# Sheet1.net
KiCad netlist of a schematic drawn in Altium Designer
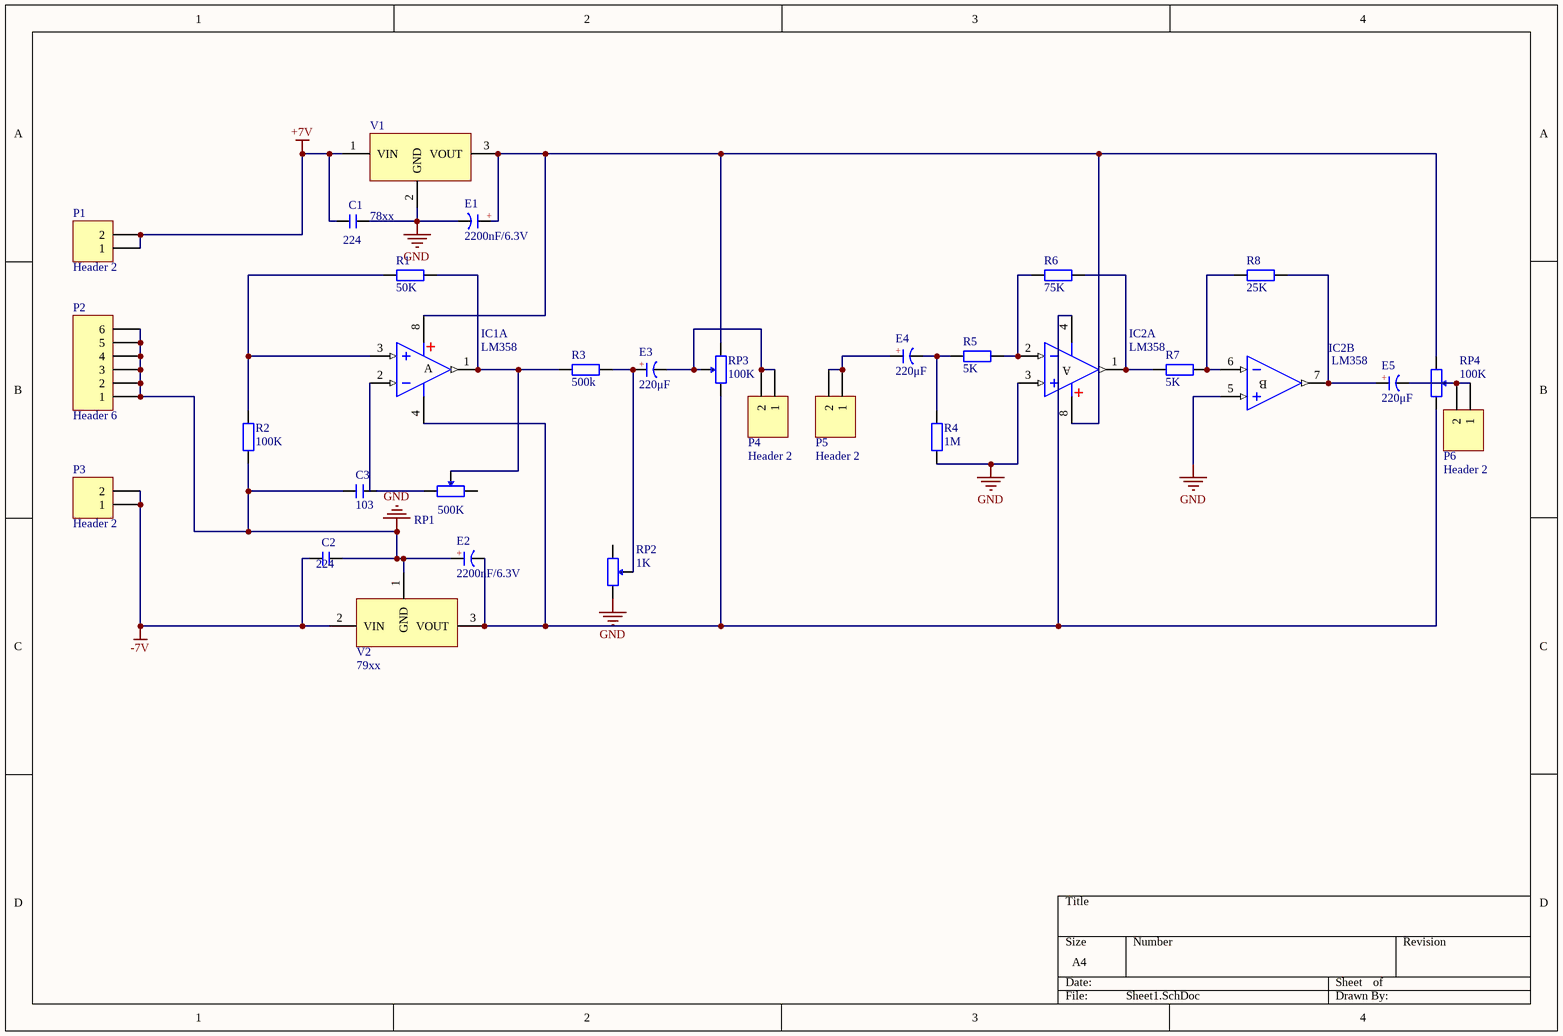
[diagram p0: Sheet1.SchDoc]

(export (version "E")
  (design (tool "Eeschema 10.0.6"))
  (components
    (comp (ref "C1")
      (value "224")
      (footprint "C 0805_L")
      (description "无极性贴片电容")
      (fields (field (name "版权归属") "源创客"))
      (libsource (lib "3.1   - 电阻-电容-电感") (part "C"))
    )
    (comp (ref "C2")
      (value "224")
      (footprint "C 0805_L")
      (description "无极性贴片电容")
      (fields (field (name "版权归属") "源创客"))
      (libsource (lib "3.1   - 电阻-电容-电感") (part "C"))
    )
    (comp (ref "C3")
      (value "103")
      (footprint "C 0805_L")
      (description "无极性贴片电容")
      (fields (field (name "版权归属") "源创客"))
      (libsource (lib "3.1   - 电阻-电容-电感") (part "C"))
    )
    (comp (ref "E1")
      (value "2200nF/6.3V")
      (footprint "CS 5.0*10*13 - C")
      (description "直插固态电容")
      (fields (field (name "版权归属") "源创客"))
      (libsource (lib "") (part "C-CS_1"))
    )
    (comp (ref "E2")
      (value "2200nF/6.3V")
      (footprint "CS 5.0*10*13 - C")
      (description "直插固态电容")
      (fields (field (name "版权归属") "源创客"))
      (libsource (lib "3.1   - 电阻-电容-电感") (part "C-CS"))
    )
    (comp (ref "E3")
      (value "220μF")
      (footprint "CS 2.5*6.3*11 - C")
      (description "直插固态电容")
      (fields (field (name "版权归属") "源创客"))
      (libsource (lib "3.1   - 电阻-电容-电感") (part "C-CS"))
    )
    (comp (ref "E4")
      (value "220μF")
      (footprint "CS 2.0*5*8 - C")
      (description "直插固态电容")
      (fields (field (name "版权归属") "源创客"))
      (libsource (lib "3.1   - 电阻-电容-电感") (part "C-CS"))
    )
    (comp (ref "E5")
      (value "220μF")
      (footprint "CS 2.0*5*8 - C")
      (description "直插固态电容")
      (fields (field (name "版权归属") "源创客"))
      (libsource (lib "3.1   - 电阻-电容-电感") (part "C-CS"))
    )
    (comp (ref "IC1")
      (value "LM358")
      (footprint "SOP8_N")
      (description "双路运放")
      (fields (field (name "版权归属") "源创客"))
      (libsource (lib "1.1   - IC芯片") (part "LM358"))
    )
    (comp (ref "IC2")
      (value "LM358")
      (footprint "SOP8_N")
      (description "双路运放")
      (fields (field (name "版权归属") "源创客"))
      (libsource (lib "1.1   - IC芯片") (part "LM358"))
    )
    (comp (ref "P1")
      (value "Header 2")
      (footprint "HDR1X2")
      (description "Header, 2-Pin")
      (fields (field (name "PUBLISHER") "Altium Limited"))
      (libsource (lib "") (part "Header 2_1"))
    )
    (comp (ref "P2")
      (value "Header 6")
      (footprint "HDR1X6")
      (description "Header, 6-Pin")
      (fields (field (name "PUBLISHER") "Altium Limited"))
      (libsource (lib "Miscellaneous Connectors") (part "Header 6"))
    )
    (comp (ref "P3")
      (value "Header 2")
      (footprint "HDR1X2")
      (description "Header, 2-Pin")
      (fields (field (name "PUBLISHER") "Altium Limited"))
      (libsource (lib "") (part "Header 2_1"))
    )
    (comp (ref "P4")
      (value "Header 2")
      (footprint "HDR1X2")
      (description "Header, 2-Pin")
      (fields (field (name "PUBLISHER") "Altium Limited"))
      (libsource (lib "Miscellaneous Connectors") (part "Header 2"))
    )
    (comp (ref "P5")
      (value "Header 2")
      (footprint "HDR1X2")
      (description "Header, 2-Pin")
      (fields (field (name "PUBLISHER") "Altium Limited"))
      (libsource (lib "Miscellaneous Connectors") (part "Header 2"))
    )
    (comp (ref "P6")
      (value "Header 2")
      (footprint "HDR1X2")
      (description "Header, 2-Pin")
      (fields (field (name "PUBLISHER") "Altium Limited"))
      (libsource (lib "Miscellaneous Connectors") (part "Header 2"))
    )
    (comp (ref "R1")
      (value "50K")
      (footprint "R 0805-HP_L")
      (description "精密贴片电阻")
      (fields (field (name "版权归属") "源创客"))
      (libsource (lib "3.1   - 电阻-电容-电感") (part "R-Precision"))
    )
    (comp (ref "R2")
      (value "100K")
      (footprint "R 0805-HP_L")
      (description "精密贴片电阻")
      (fields (field (name "版权归属") "源创客"))
      (libsource (lib "3.1   - 电阻-电容-电感") (part "R-Precision"))
    )
    (comp (ref "R3")
      (value "500k")
      (footprint "RS 1/4W")
      (description "直插色环电阻")
      (fields (field (name "版权归属") "源创客"))
      (libsource (lib "3.1   - 电阻-电容-电感") (part "R-CRR"))
    )
    (comp (ref "R4")
      (value "1M")
      (footprint "RS 1/4W")
      (description "直插色环电阻")
      (fields (field (name "版权归属") "源创客"))
      (libsource (lib "3.1   - 电阻-电容-电感") (part "R-CRR"))
    )
    (comp (ref "R5")
      (value "5K")
      (footprint "R 0805_L")
      (description "贴片电阻")
      (fields (field (name "版权归属") "源创客"))
      (libsource (lib "3.1   - 电阻-电容-电感") (part "R"))
    )
    (comp (ref "R6")
      (value "75K")
      (footprint "R 0805_L")
      (description "贴片电阻")
      (fields (field (name "版权归属") "源创客"))
      (libsource (lib "3.1   - 电阻-电容-电感") (part "R"))
    )
    (comp (ref "R7")
      (value "5K")
      (footprint "R 0805_L")
      (description "贴片电阻")
      (fields (field (name "版权归属") "源创客"))
      (libsource (lib "3.1   - 电阻-电容-电感") (part "R"))
    )
    (comp (ref "R8")
      (value "25K")
      (footprint "R 0805_L")
      (description "贴片电阻")
      (fields (field (name "版权归属") "源创客"))
      (libsource (lib "3.1   - 电阻-电容-电感") (part "R"))
    )
    (comp (ref "RP1")
      (value "500K")
      (footprint "3296W")
      (description "插件单联电位器")
      (fields (field (name "版权归属") "源创客"))
      (libsource (lib "3.1   - 电阻-电容-电感") (part "RP-ID"))
    )
    (comp (ref "RP2")
      (value "1K")
      (footprint "3296W")
      (description "插件单联电位器")
      (fields (field (name "版权归属") "源创客"))
      (libsource (lib "3.1   - 电阻-电容-电感") (part "RP-ID"))
    )
    (comp (ref "RP3")
      (value "100K")
      (footprint "3296W")
      (description "插件单联电位器")
      (fields (field (name "版权归属") "源创客"))
      (libsource (lib "3.1   - 电阻-电容-电感") (part "RP-ID"))
    )
    (comp (ref "RP4")
      (value "100K")
      (footprint "3296W")
      (description "插件单联电位器")
      (fields (field (name "版权归属") "源创客"))
      (libsource (lib "3.1   - 电阻-电容-电感") (part "RP-ID"))
    )
    (comp (ref "V1")
      (value "78xx")
      (footprint "TO220A")
      (description "线性稳压芯片")
      (fields (field (name "版权归属") "源创客"))
      (libsource (lib "1.3   - 电源类芯片") (part "78xx"))
    )
    (comp (ref "V2")
      (value "79xx")
      (footprint "TO220A")
      (description "线性稳压芯片")
      (fields (field (name "版权归属") "源创客"))
      (libsource (lib "1.3   - 电源类芯片") (part "79xx"))
    )
  )
  (nets
    (net (code "1") (name "+7V") (class "Default")
      (node (ref "C1") (pin "1") (pinfunction "1_1") (pintype "passive"))
      (node (ref "P1") (pin "1") (pinfunction "1_1") (pintype "passive"))
      (node (ref "P1") (pin "2") (pinfunction "2_2") (pintype "passive"))
      (node (ref "V1") (pin "1") (pinfunction "VIN_1") (pintype "passive"))
    )
    (net (code "2") (name "-7V") (class "Default")
      (node (ref "C2") (pin "1") (pinfunction "1_1") (pintype "passive"))
      (node (ref "P3") (pin "1") (pinfunction "1_1") (pintype "passive"))
      (node (ref "P3") (pin "2") (pinfunction "2_2") (pintype "passive"))
      (node (ref "V2") (pin "2") (pinfunction "VIN_2") (pintype "passive"))
    )
    (net (code "3") (name "GND") (class "Default")
      (node (ref "C1") (pin "2") (pinfunction "2_2") (pintype "passive"))
      (node (ref "C2") (pin "2") (pinfunction "2_2") (pintype "passive"))
      (node (ref "C3") (pin "1") (pinfunction "1_1") (pintype "passive"))
      (node (ref "E1") (pin "2") (pinfunction "K_2") (pintype "passive"))
      (node (ref "E2") (pin "1") (pinfunction "A_1") (pintype "passive"))
      (node (ref "IC2") (pin "3") (pinfunction "IN+_3") (pintype "input"))
      (node (ref "IC2") (pin "5") (pinfunction "IN+_5") (pintype "input"))
      (node (ref "P2") (pin "1") (pinfunction "1_1") (pintype "passive"))
      (node (ref "P2") (pin "2") (pinfunction "2_2") (pintype "passive"))
      (node (ref "P2") (pin "3") (pinfunction "3_3") (pintype "passive"))
      (node (ref "P2") (pin "4") (pinfunction "4_4") (pintype "passive"))
      (node (ref "P2") (pin "5") (pinfunction "5_5") (pintype "passive"))
      (node (ref "P2") (pin "6") (pinfunction "6_6") (pintype "passive"))
      (node (ref "R2") (pin "1") (pinfunction "1_1") (pintype "passive"))
      (node (ref "R4") (pin "1") (pinfunction "1_1") (pintype "passive"))
      (node (ref "RP2") (pin "3") (pinfunction "3_3") (pintype "passive"))
      (node (ref "V1") (pin "2") (pinfunction "GND_2") (pintype "passive"))
      (node (ref "V2") (pin "1") (pinfunction "GND_1") (pintype "passive"))
    )
    (net (code "4") (name "Net-(C3-Pad2)") (class "Default")
      (node (ref "C3") (pin "2") (pinfunction "2_2") (pintype "passive"))
      (node (ref "RP1") (pin "1") (pinfunction "1_1") (pintype "passive"))
    )
    (net (code "5") (name "Net-(E1-A)") (class "Default")
      (node (ref "E1") (pin "1") (pinfunction "A_1") (pintype "passive"))
      (node (ref "IC1") (pin "8") (pinfunction "V+_8") (pintype "power_in"))
      (node (ref "IC2") (pin "8") (pinfunction "V+_8") (pintype "power_in"))
      (node (ref "RP3") (pin "3") (pinfunction "3_3") (pintype "passive"))
      (node (ref "RP4") (pin "1") (pinfunction "1_1") (pintype "passive"))
      (node (ref "V1") (pin "3") (pinfunction "VOUT_3") (pintype "passive"))
    )
    (net (code "6") (name "Net-(E2-K)") (class "Default")
      (node (ref "E2") (pin "2") (pinfunction "K_2") (pintype "passive"))
      (node (ref "IC1") (pin "4") (pinfunction "V-_4") (pintype "power_in"))
      (node (ref "IC2") (pin "4") (pinfunction "V-_4") (pintype "power_in"))
      (node (ref "RP3") (pin "1") (pinfunction "1_1") (pintype "passive"))
      (node (ref "RP4") (pin "3") (pinfunction "3_3") (pintype "passive"))
      (node (ref "V2") (pin "3") (pinfunction "VOUT_3") (pintype "passive"))
    )
    (net (code "7") (name "Net-(E3-A)") (class "Default")
      (node (ref "E3") (pin "1") (pinfunction "A_1") (pintype "passive"))
      (node (ref "R3") (pin "1") (pinfunction "1_1") (pintype "passive"))
      (node (ref "RP2") (pin "2") (pinfunction "2_2") (pintype "passive"))
    )
    (net (code "8") (name "Net-(E3-K)") (class "Default")
      (node (ref "E3") (pin "2") (pinfunction "K_2") (pintype "passive"))
      (node (ref "P4") (pin "1") (pinfunction "1_1") (pintype "passive"))
      (node (ref "P4") (pin "2") (pinfunction "2_2") (pintype "passive"))
      (node (ref "RP3") (pin "2") (pinfunction "2_2") (pintype "passive"))
    )
    (net (code "9") (name "Net-(E4-A)") (class "Default")
      (node (ref "E4") (pin "1") (pinfunction "A_1") (pintype "passive"))
      (node (ref "P5") (pin "1") (pinfunction "1_1") (pintype "passive"))
      (node (ref "P5") (pin "2") (pinfunction "2_2") (pintype "passive"))
    )
    (net (code "10") (name "Net-(E4-K)") (class "Default")
      (node (ref "E4") (pin "2") (pinfunction "K_2") (pintype "passive"))
      (node (ref "R4") (pin "2") (pinfunction "2_2") (pintype "passive"))
      (node (ref "R5") (pin "1") (pinfunction "1_1") (pintype "passive"))
    )
    (net (code "11") (name "Net-(E5-A)") (class "Default")
      (node (ref "E5") (pin "1") (pinfunction "A_1") (pintype "passive"))
      (node (ref "IC2") (pin "7") (pinfunction "OUT_7") (pintype "output"))
      (node (ref "R8") (pin "2") (pinfunction "2_2") (pintype "passive"))
    )
    (net (code "12") (name "Net-(E5-K)") (class "Default")
      (node (ref "E5") (pin "2") (pinfunction "K_2") (pintype "passive"))
      (node (ref "P6") (pin "1") (pinfunction "1_1") (pintype "passive"))
      (node (ref "P6") (pin "2") (pinfunction "2_2") (pintype "passive"))
      (node (ref "RP4") (pin "2") (pinfunction "2_2") (pintype "passive"))
    )
    (net (code "13") (name "Net-(IC1A-IN+)") (class "Default")
      (node (ref "IC1") (pin "3") (pinfunction "IN+_3") (pintype "input"))
      (node (ref "R1") (pin "2") (pinfunction "2_2") (pintype "passive"))
      (node (ref "R2") (pin "2") (pinfunction "2_2") (pintype "passive"))
    )
    (net (code "14") (name "Net-(IC1A-OUT)") (class "Default")
      (node (ref "IC1") (pin "1") (pinfunction "OUT_1") (pintype "output"))
      (node (ref "R1") (pin "1") (pinfunction "1_1") (pintype "passive"))
      (node (ref "R3") (pin "2") (pinfunction "2_2") (pintype "passive"))
      (node (ref "RP1") (pin "2") (pinfunction "2_2") (pintype "passive"))
    )
    (net (code "15") (name "Net-(IC2A-IN-)") (class "Default")
      (node (ref "IC2") (pin "2") (pinfunction "IN-_2") (pintype "input"))
      (node (ref "R5") (pin "2") (pinfunction "2_2") (pintype "passive"))
      (node (ref "R6") (pin "1") (pinfunction "1_1") (pintype "passive"))
    )
    (net (code "16") (name "Net-(IC2A-OUT)") (class "Default")
      (node (ref "IC2") (pin "1") (pinfunction "OUT_1") (pintype "output"))
      (node (ref "R6") (pin "2") (pinfunction "2_2") (pintype "passive"))
      (node (ref "R7") (pin "1") (pinfunction "1_1") (pintype "passive"))
    )
    (net (code "17") (name "Net-(IC2B-IN-)") (class "Default")
      (node (ref "IC2") (pin "6") (pinfunction "IN-_6") (pintype "input"))
      (node (ref "R7") (pin "2") (pinfunction "2_2") (pintype "passive"))
      (node (ref "R8") (pin "1") (pinfunction "1_1") (pintype "passive"))
    )
    (net (code "18") (name "unconnected-(IC1A-IN--Pad2)") (class "Default")
      (node (ref "IC1") (pin "2") (pinfunction "IN-_2") (pintype "input"))
    )
    (net (code "19") (name "unconnected-(RP1-Pad3)") (class "Default")
      (node (ref "RP1") (pin "3") (pinfunction "3_3") (pintype "passive"))
    )
    (net (code "20") (name "unconnected-(RP2-Pad1)") (class "Default")
      (node (ref "RP2") (pin "1") (pinfunction "1_1") (pintype "passive"))
    )
  )
)
